# SparkFun_MicroMod_GNSS_Function_Board_ZE.net
KiCad netlist of a schematic drawn in EAGLE
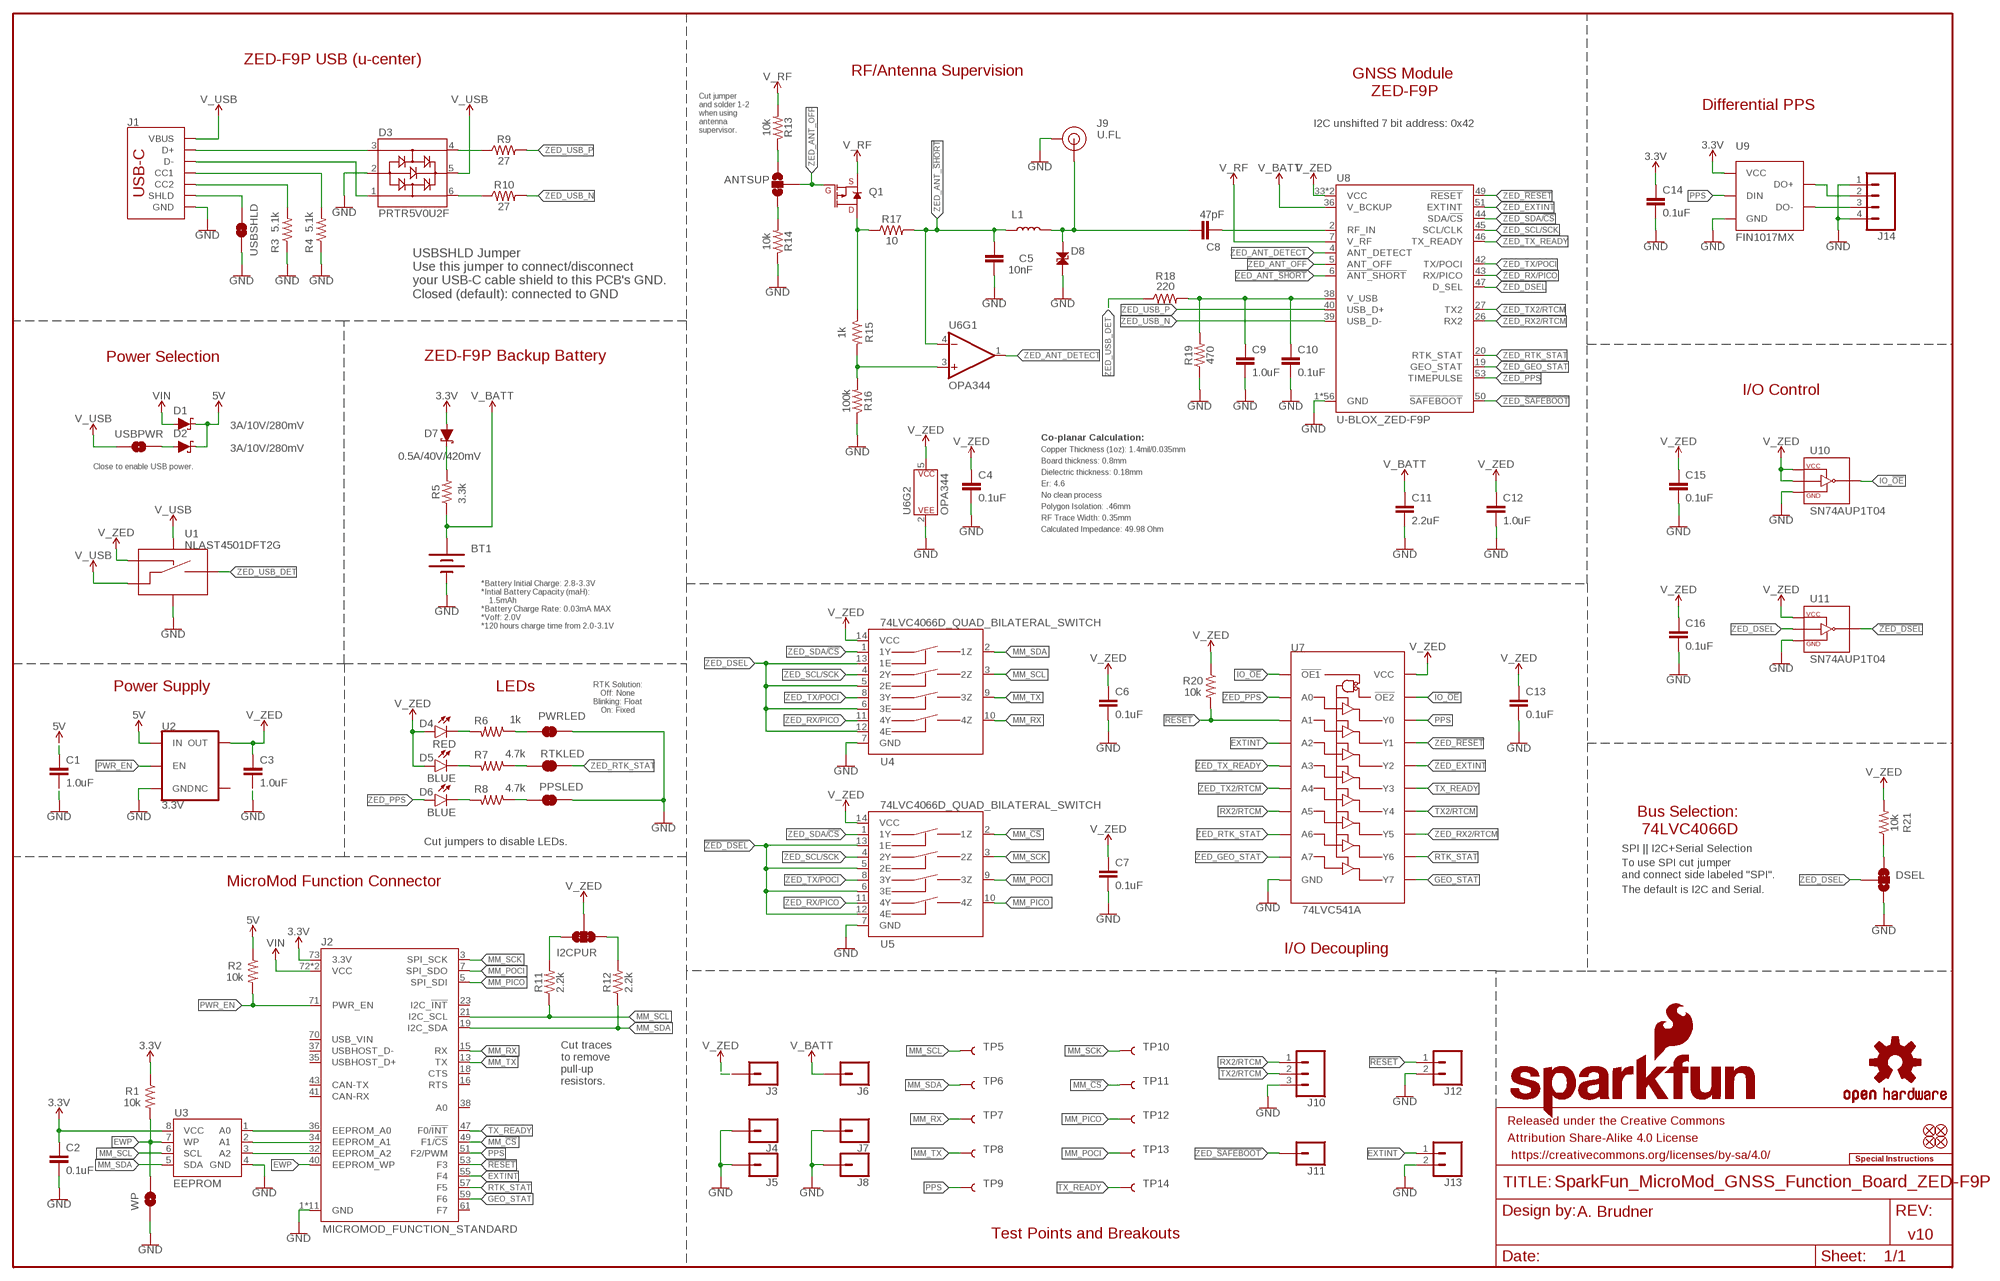
[diagram p0: schematic, sheet 1]

(export (version "E")
  (design (tool "Eeschema 10.0.6"))
  (components
    (comp (ref "ANTSUP")
      (value "JUMPER-SMT_3_1-NC_TRACE_SILK")
      (footprint "eagle-import:SMT-JUMPER_3_1-NC_TRACE_SILK")
      (libsource (lib "eagle-import") (part "JUMPER-SMT_3_1-NC_TRACE_SILK"))
    )
    (comp (ref "BT1")
      (value "RELOWABLE_BATTERY_MS421R")
      (footprint "eagle-import:MS421R_IV03E")
      (libsource (lib "eagle-import") (part "RELOWABLE_BATTERY_MS421R"))
    )
    (comp (ref "C1")
      (value "1.0uF")
      (footprint "eagle-import:0402-TIGHT")
      (libsource (lib "eagle-import") (part "1.0UF-0402T-16V-10%"))
    )
    (comp (ref "C2")
      (value "0.1uF")
      (footprint "eagle-import:0402-TIGHT")
      (libsource (lib "eagle-import") (part "0.1UF-0402T-16V-10%"))
    )
    (comp (ref "C3")
      (value "1.0uF")
      (footprint "eagle-import:0402-TIGHT")
      (libsource (lib "eagle-import") (part "1.0UF-0402T-16V-10%"))
    )
    (comp (ref "C4")
      (value "0.1uF")
      (footprint "eagle-import:0402-TIGHT")
      (libsource (lib "eagle-import") (part "0.1UF-0402T-16V-10%"))
    )
    (comp (ref "C5")
      (value "10nF")
      (footprint "eagle-import:0402-TIGHT")
      (libsource (lib "eagle-import") (part "10NF-0402T-25V-10%-X7R-WE"))
    )
    (comp (ref "C6")
      (value "0.1uF")
      (footprint "eagle-import:0402-TIGHT")
      (libsource (lib "eagle-import") (part "0.1UF-0402T-16V-10%"))
    )
    (comp (ref "C7")
      (value "0.1uF")
      (footprint "eagle-import:0402-TIGHT")
      (libsource (lib "eagle-import") (part "0.1UF-0402T-16V-10%"))
    )
    (comp (ref "C8")
      (value "47pF")
      (footprint "eagle-import:0402-TIGHT")
      (fields
        (field (name "TOLERANCE") "5%")
        (field (name "VOLTAGE") "50V")
        (field (name "CAPACITANCE") "47pF")
      )
      (libsource (lib "eagle-import") (part "CBR04C470J5GAC"))
    )
    (comp (ref "C9")
      (value "1.0uF")
      (footprint "eagle-import:0402-TIGHT")
      (libsource (lib "eagle-import") (part "1.0UF-0402T-16V-10%"))
    )
    (comp (ref "C10")
      (value "0.1uF")
      (footprint "eagle-import:0402-TIGHT")
      (libsource (lib "eagle-import") (part "0.1UF-0402T-16V-10%"))
    )
    (comp (ref "C11")
      (value "2.2uF")
      (footprint "eagle-import:0402-TIGHT")
      (libsource (lib "eagle-import") (part "2.2UF-0402_TIGHT-10V-10%-X5R"))
    )
    (comp (ref "C12")
      (value "1.0uF")
      (footprint "eagle-import:0402-TIGHT")
      (libsource (lib "eagle-import") (part "1.0UF-0402T-16V-10%"))
    )
    (comp (ref "C13")
      (value "0.1uF")
      (footprint "eagle-import:0402-TIGHT")
      (libsource (lib "eagle-import") (part "0.1UF-0402T-16V-10%"))
    )
    (comp (ref "C14")
      (value "0.1uF")
      (footprint "eagle-import:0402-TIGHT")
      (libsource (lib "eagle-import") (part "0.1UF-0402T-16V-10%"))
    )
    (comp (ref "C15")
      (value "0.1uF")
      (footprint "eagle-import:0402-TIGHT")
      (libsource (lib "eagle-import") (part "0.1UF-0402T-16V-10%"))
    )
    (comp (ref "C16")
      (value "0.1uF")
      (footprint "eagle-import:0402-TIGHT")
      (libsource (lib "eagle-import") (part "0.1UF-0402T-16V-10%"))
    )
    (comp (ref "D1")
      (value "3A/10V/280mV")
      (footprint "eagle-import:SOD-323")
      (libsource (lib "eagle-import") (part "DIODE-SCHOTTKY-BAT60A"))
    )
    (comp (ref "D2")
      (value "3A/10V/280mV")
      (footprint "eagle-import:SOD-323")
      (libsource (lib "eagle-import") (part "DIODE-SCHOTTKY-BAT60A"))
    )
    (comp (ref "D3")
      (value "PRTR5V0U2F")
      (footprint "eagle-import:SOT886")
      (libsource (lib "eagle-import") (part "PRTR5V0U2F"))
    )
    (comp (ref "D4")
      (value "RED")
      (footprint "eagle-import:LED-0603")
      (libsource (lib "eagle-import") (part "LED-RED0603"))
    )
    (comp (ref "D5")
      (value "BLUE")
      (footprint "eagle-import:LED-0603")
      (libsource (lib "eagle-import") (part "LED-BLUE0603"))
    )
    (comp (ref "D6")
      (value "BLUE")
      (footprint "eagle-import:LED-0603")
      (libsource (lib "eagle-import") (part "LED-BLUE0603"))
    )
    (comp (ref "D7")
      (value "0.5A/40V/420mV")
      (footprint "eagle-import:SOD-323")
      (libsource (lib "eagle-import") (part "DIODE-SCHOTTKY-PMEG4005EJ"))
    )
    (comp (ref "D8")
      (value "PESD0402-0402T")
      (footprint "eagle-import:0402-TIGHT")
      (libsource (lib "eagle-import") (part "PESD0402-0402T"))
    )
    (comp (ref "DSEL")
      (value "JUMPER-SMT_3_1-NC_TRACE_SILK")
      (footprint "eagle-import:SMT-JUMPER_3_1-NC_TRACE_SILK")
      (libsource (lib "eagle-import") (part "JUMPER-SMT_3_1-NC_TRACE_SILK"))
    )
    (comp (ref "FD1")
      (value "FIDUCIALUFIDUCIAL")
      (footprint "eagle-import:FIDUCIAL-MICRO")
      (libsource (lib "eagle-import") (part "FIDUCIALUFIDUCIAL"))
    )
    (comp (ref "FD2")
      (value "FIDUCIALUFIDUCIAL")
      (footprint "eagle-import:FIDUCIAL-MICRO")
      (libsource (lib "eagle-import") (part "FIDUCIALUFIDUCIAL"))
    )
    (comp (ref "FD3")
      (value "FIDUCIALUFIDUCIAL")
      (footprint "eagle-import:FIDUCIAL-MICRO")
      (libsource (lib "eagle-import") (part "FIDUCIALUFIDUCIAL"))
    )
    (comp (ref "FD4")
      (value "FIDUCIALUFIDUCIAL")
      (footprint "eagle-import:FIDUCIAL-MICRO")
      (libsource (lib "eagle-import") (part "FIDUCIALUFIDUCIAL"))
    )
    (comp (ref "FRAME1")
      (value "FRAME-LEDGER")
      (footprint "eagle-import:CREATIVE_COMMONS")
      (libsource (lib "eagle-import") (part "FRAME-LEDGER"))
    )
    (comp (ref "I2CPUR")
      (value "JUMPER-SMT_3_2-NC_TRACE_SILK")
      (footprint "eagle-import:SMT-JUMPER_3_2-NC_TRACE_SILK")
      (libsource (lib "eagle-import") (part "JUMPER-SMT_3_2-NC_TRACE_SILK"))
    )
    (comp (ref "J1")
      (value "USB Female Type C Connector")
      (footprint "eagle-import:USB-C-16P-4LAYER-ISOLATED")
      (libsource (lib "eagle-import") (part "USB_C_4-LAYER-ISOLATED"))
    )
    (comp (ref "J2")
      (value "MICROMOD_FUNCTION_STANDARD")
      (footprint "eagle-import:M.2-CARD-E-22_FUNCTION_STANDARD")
      (libsource (lib "eagle-import") (part "MICROMOD_FUNCTION_STANDARD"))
    )
    (comp (ref "J3")
      (value "CONN_01PTH_NO_SILK_YES_STOP")
      (footprint "eagle-import:1X01_NO_SILK")
      (libsource (lib "eagle-import") (part "CONN_01PTH_NO_SILK_YES_STOP"))
    )
    (comp (ref "J4")
      (value "CONN_01PTH_NO_SILK_YES_STOP")
      (footprint "eagle-import:1X01_NO_SILK")
      (libsource (lib "eagle-import") (part "CONN_01PTH_NO_SILK_YES_STOP"))
    )
    (comp (ref "J5")
      (value "CONN_01PTH_NO_SILK_YES_STOP")
      (footprint "eagle-import:1X01_NO_SILK")
      (libsource (lib "eagle-import") (part "CONN_01PTH_NO_SILK_YES_STOP"))
    )
    (comp (ref "J6")
      (value "CONN_01PTH_NO_SILK_SMALL")
      (footprint "eagle-import:1X01_SMALL")
      (libsource (lib "eagle-import") (part "CONN_01PTH_NO_SILK_SMALL"))
    )
    (comp (ref "J7")
      (value "CONN_01PTH_NO_SILK_YES_STOP")
      (footprint "eagle-import:1X01_NO_SILK")
      (libsource (lib "eagle-import") (part "CONN_01PTH_NO_SILK_YES_STOP"))
    )
    (comp (ref "J8")
      (value "CONN_01PTH_NO_SILK_YES_STOP")
      (footprint "eagle-import:1X01_NO_SILK")
      (libsource (lib "eagle-import") (part "CONN_01PTH_NO_SILK_YES_STOP"))
    )
    (comp (ref "J9")
      (value "U.FL")
      (footprint "eagle-import:U.FL")
      (libsource (lib "eagle-import") (part "U.FL2PIN"))
    )
    (comp (ref "J10")
      (value "455-1750-1-ND")
      (footprint "eagle-import:1X03_NO_SILK")
      (libsource (lib "eagle-import") (part "CONN_031X03_NO_SILK"))
    )
    (comp (ref "J11")
      (value "CONN_01PTH_NO_SILK_YES_STOP")
      (footprint "eagle-import:1X01_NO_SILK")
      (libsource (lib "eagle-import") (part "CONN_01PTH_NO_SILK_YES_STOP"))
    )
    (comp (ref "J12")
      (value "CONN_021X02_NO_SILK")
      (footprint "eagle-import:1X02_NO_SILK")
      (libsource (lib "eagle-import") (part "CONN_021X02_NO_SILK"))
    )
    (comp (ref "J13")
      (value "CONN_021X02_NO_SILK")
      (footprint "eagle-import:1X02_NO_SILK")
      (libsource (lib "eagle-import") (part "CONN_021X02_NO_SILK"))
    )
    (comp (ref "J14")
      (value "CONN_041X04_NO_SILK")
      (footprint "eagle-import:1X04_NO_SILK")
      (libsource (lib "eagle-import") (part "CONN_041X04_NO_SILK"))
    )
    (comp (ref "L1")
      (value "150nH")
      (footprint "eagle-import:0402_MURATA")
      (libsource (lib "eagle-import") (part "LQW15AWR15J80D"))
    )
    (comp (ref "LOGO1")
      (value "SFE_LOGO_NAME_FLAMEBLANK")
      (footprint "eagle-import:BLANK")
      (libsource (lib "eagle-import") (part "SFE_LOGO_NAME_FLAMEBLANK"))
    )
    (comp (ref "LOGO2")
      (value "SPECIAL_INSTRUCTIONS-ORDERING")
      (footprint "eagle-import:ORDERING_INSTRUCTIONS")
      (libsource (lib "eagle-import") (part "SPECIAL_INSTRUCTIONS-ORDERING"))
    )
    (comp (ref "LOGO3")
      (value "OSHW-LOGOMINI")
      (footprint "eagle-import:OSHW-LOGO-MINI")
      (libsource (lib "eagle-import") (part "OSHW-LOGOMINI"))
    )
    (comp (ref "PPSLED")
      (value "JUMPER-SMT_2_NC_TRACE_SILK")
      (footprint "eagle-import:SMT-JUMPER_2_NC_TRACE_SILK")
      (libsource (lib "eagle-import") (part "JUMPER-SMT_2_NC_TRACE_SILK"))
    )
    (comp (ref "PWRLED")
      (value "JUMPER-SMT_2_NC_TRACE_SILK")
      (footprint "eagle-import:SMT-JUMPER_2_NC_TRACE_SILK")
      (libsource (lib "eagle-import") (part "JUMPER-SMT_2_NC_TRACE_SILK"))
    )
    (comp (ref "Q1")
      (value "DMP21D0UT-7")
      (footprint "eagle-import:SOT523")
      (libsource (lib "eagle-import") (part "DMP21D0UT-7"))
    )
    (comp (ref "R1")
      (value "10k")
      (footprint "eagle-import:0402-TIGHT")
      (libsource (lib "eagle-import") (part "10KOHM-0402T-1/16W-1%"))
    )
    (comp (ref "R2")
      (value "10k")
      (footprint "eagle-import:0402-TIGHT")
      (libsource (lib "eagle-import") (part "10KOHM-0402T-1/16W-1%"))
    )
    (comp (ref "R3")
      (value "5.1k")
      (footprint "eagle-import:0402-TIGHT")
      (libsource (lib "eagle-import") (part "5.1KOHM-0402T-1/16W-1%"))
    )
    (comp (ref "R4")
      (value "5.1k")
      (footprint "eagle-import:0402-TIGHT")
      (libsource (lib "eagle-import") (part "5.1KOHM-0402T-1/16W-1%"))
    )
    (comp (ref "R5")
      (value "3.3K")
      (footprint "eagle-import:0402-TIGHT")
      (fields (field (name "RES") "3.3k"))
      (libsource (lib "eagle-import") (part "3.3KOHM-0402T-1/16W-1%"))
    )
    (comp (ref "R6")
      (value "1k")
      (footprint "eagle-import:0402-TIGHT")
      (libsource (lib "eagle-import") (part "1KOHM-0402T-1/16W-1%"))
    )
    (comp (ref "R7")
      (value "4.7k")
      (footprint "eagle-import:0402-TIGHT")
      (libsource (lib "eagle-import") (part "4.7KOHM-0402T-1/16W-1%"))
    )
    (comp (ref "R8")
      (value "4.7k")
      (footprint "eagle-import:0402-TIGHT")
      (libsource (lib "eagle-import") (part "4.7KOHM-0402T-1/16W-1%"))
    )
    (comp (ref "R9")
      (value "27")
      (footprint "eagle-import:0402-TIGHT")
      (libsource (lib "eagle-import") (part "27OHM"))
    )
    (comp (ref "R10")
      (value "27")
      (footprint "eagle-import:0402-TIGHT")
      (libsource (lib "eagle-import") (part "27OHM"))
    )
    (comp (ref "R11")
      (value "2.2k")
      (footprint "eagle-import:0402-TIGHT")
      (libsource (lib "eagle-import") (part "2.2KOHM-0402T-1/16W-1%"))
    )
    (comp (ref "R12")
      (value "2.2k")
      (footprint "eagle-import:0402-TIGHT")
      (libsource (lib "eagle-import") (part "2.2KOHM-0402T-1/16W-1%"))
    )
    (comp (ref "R13")
      (value "10k")
      (footprint "eagle-import:0402-TIGHT")
      (libsource (lib "eagle-import") (part "10KOHM-0402T-1/16W-1%"))
    )
    (comp (ref "R14")
      (value "10k")
      (footprint "eagle-import:0402-TIGHT")
      (libsource (lib "eagle-import") (part "10KOHM-0402T-1/16W-1%"))
    )
    (comp (ref "R15")
      (value "1k")
      (footprint "eagle-import:0402-TIGHT")
      (fields (field (name "RESISTANCE") "1k"))
      (libsource (lib "eagle-import") (part "1KOHM-0402T-1/16W-1%"))
    )
    (comp (ref "R16")
      (value "100k")
      (footprint "eagle-import:0402-TIGHT")
      (libsource (lib "eagle-import") (part "100KOHM-0402T-1/16W-1%"))
    )
    (comp (ref "R17")
      (value "10")
      (footprint "eagle-import:0603")
      (libsource (lib "eagle-import") (part "10OHM-0603-1/10W-1%"))
    )
    (comp (ref "R18")
      (value "220")
      (footprint "eagle-import:0402-TIGHT")
      (libsource (lib "eagle-import") (part "220OHM-0402-TIGHT-1/16W-1%"))
    )
    (comp (ref "R19")
      (value "470")
      (footprint "eagle-import:0402-TIGHT")
      (libsource (lib "eagle-import") (part "470OHM-0402-TIGHT-1/16W-1%"))
    )
    (comp (ref "R20")
      (value "10k")
      (footprint "eagle-import:0402-TIGHT")
      (libsource (lib "eagle-import") (part "10KOHM-0402T-1/16W-1%"))
    )
    (comp (ref "R21")
      (value "10k")
      (footprint "eagle-import:0402-TIGHT")
      (libsource (lib "eagle-import") (part "10KOHM-0402T-1/16W-1%"))
    )
    (comp (ref "RTKLED")
      (value "JUMPER-SMT_2_NC_TRACE_SILK")
      (footprint "eagle-import:SMT-JUMPER_2_NC_TRACE_SILK")
      (libsource (lib "eagle-import") (part "JUMPER-SMT_2_NC_TRACE_SILK"))
    )
    (comp (ref "TP5")
      (value "TEST-POINT3")
      (footprint "eagle-import:PAD.03X.03")
      (libsource (lib "eagle-import") (part "TEST-POINT3"))
    )
    (comp (ref "TP6")
      (value "TEST-POINT3")
      (footprint "eagle-import:PAD.03X.03")
      (libsource (lib "eagle-import") (part "TEST-POINT3"))
    )
    (comp (ref "TP7")
      (value "TEST-POINT3")
      (footprint "eagle-import:PAD.03X.03")
      (libsource (lib "eagle-import") (part "TEST-POINT3"))
    )
    (comp (ref "TP8")
      (value "TEST-POINT3")
      (footprint "eagle-import:PAD.03X.03")
      (libsource (lib "eagle-import") (part "TEST-POINT3"))
    )
    (comp (ref "TP9")
      (value "TEST-POINT3")
      (footprint "eagle-import:PAD.03X.03")
      (libsource (lib "eagle-import") (part "TEST-POINT3"))
    )
    (comp (ref "TP10")
      (value "TEST-POINT3")
      (footprint "eagle-import:PAD.03X.03")
      (libsource (lib "eagle-import") (part "TEST-POINT3"))
    )
    (comp (ref "TP11")
      (value "TEST-POINT3")
      (footprint "eagle-import:PAD.03X.03")
      (libsource (lib "eagle-import") (part "TEST-POINT3"))
    )
    (comp (ref "TP12")
      (value "TEST-POINT3")
      (footprint "eagle-import:PAD.03X.03")
      (libsource (lib "eagle-import") (part "TEST-POINT3"))
    )
    (comp (ref "TP13")
      (value "TEST-POINT3")
      (footprint "eagle-import:PAD.03X.03")
      (libsource (lib "eagle-import") (part "TEST-POINT3"))
    )
    (comp (ref "TP14")
      (value "TEST-POINT3")
      (footprint "eagle-import:PAD.03X.03")
      (libsource (lib "eagle-import") (part "TEST-POINT3"))
    )
    (comp (ref "U1")
      (value "NLAST4501DFT2G")
      (footprint "eagle-import:SOT353")
      (libsource (lib "eagle-import") (part "NLAST4501DFT2G"))
    )
    (comp (ref "U2")
      (value "3.3V")
      (footprint "eagle-import:SOT23-5")
      (libsource (lib "eagle-import") (part "V_REG_AP2112K-3.3V"))
    )
    (comp (ref "U3")
      (value "EEPROM")
      (footprint "eagle-import:SO08")
      (libsource (lib "eagle-import") (part "EEPROM-I2C512K"))
    )
    (comp (ref "U4")
      (value "74LVC4066D_QUAD_BILATERAL_SWITCH")
      (footprint "eagle-import:SO14")
      (libsource (lib "eagle-import") (part "74LVC4066D_QUAD_BILATERAL_SWITCH"))
    )
    (comp (ref "U5")
      (value "74LVC4066D_QUAD_BILATERAL_SWITCH")
      (footprint "eagle-import:SO14")
      (libsource (lib "eagle-import") (part "74LVC4066D_QUAD_BILATERAL_SWITCH"))
    )
    (comp (ref "U6")
      (value "OPA344")
      (footprint "eagle-import:SOT23-5")
      (libsource (lib "eagle-import") (part "OPA344"))
    )
    (comp (ref "U7")
      (value "74LVC541A")
      (footprint "eagle-import:DHVQFN20")
      (libsource (lib "eagle-import") (part "74LVC541ABQ"))
    )
    (comp (ref "U8")
      (value "U-BLOX_ZED-F9P")
      (footprint "eagle-import:ZED-F9P")
      (libsource (lib "eagle-import") (part "U-BLOX_ZED-F9P"))
    )
    (comp (ref "U9")
      (value "FIN1017MX")
      (footprint "eagle-import:SO08")
      (libsource (lib "eagle-import") (part "FIN1017MX"))
    )
    (comp (ref "U10")
      (value "SN74AUP1T04")
      (footprint "eagle-import:SC-70-5_DCK")
      (libsource (lib "eagle-import") (part "SN74AUP1T04DCK"))
    )
    (comp (ref "U11")
      (value "SN74AUP1T04")
      (footprint "eagle-import:SC-70-5_DCK")
      (libsource (lib "eagle-import") (part "SN74AUP1T04DCK"))
    )
    (comp (ref "USBPWR")
      (value "JUMPER-SMT_2_NO_SILK")
      (footprint "eagle-import:SMT-JUMPER_2_NO_SILK")
      (libsource (lib "eagle-import") (part "JUMPER-SMT_2_NO_SILK"))
    )
    (comp (ref "USBSHLD")
      (value "JUMPER-SMT_2_NC_TRACE_SILK")
      (footprint "eagle-import:SMT-JUMPER_2_NC_TRACE_SILK")
      (libsource (lib "eagle-import") (part "JUMPER-SMT_2_NC_TRACE_SILK"))
    )
    (comp (ref "WP")
      (value "JUMPER-SMT_2_NO_SILK")
      (footprint "eagle-import:SMT-JUMPER_2_NO_SILK")
      (libsource (lib "eagle-import") (part "JUMPER-SMT_2_NO_SILK"))
    )
  )
  (nets
    (net (code "1") (name "/IO_~{OE}") (class "Default")
      (node (ref "U10") (pin "4") (pinfunction "Y_4") (pintype "bidirectional"))
      (node (ref "U7") (pin "1") (pinfunction "~{OE1}_1") (pintype "input"))
      (node (ref "U7") (pin "19") (pinfunction "~{OE2}_19") (pintype "input"))
    )
    (net (code "2") (name "/MM_~{CS}") (class "Default")
      (node (ref "J2") (pin "49") (pinfunction "F1/~{CS}_49") (pintype "bidirectional"))
      (node (ref "TP11") (pin "1") (pinfunction "1_1") (pintype "bidirectional"))
      (node (ref "U5") (pin "2") (pinfunction "1Z_2") (pintype "bidirectional"))
    )
    (net (code "3") (name "/ZED_ANT_~{SHORT}") (class "Default")
      (node (ref "C5") (pin "1") (pinfunction "1_1") (pintype "passive"))
      (node (ref "L1") (pin "1") (pinfunction "1_1") (pintype "passive"))
      (node (ref "R17") (pin "2") (pinfunction "2_2") (pintype "passive"))
      (node (ref "U6") (pin "4") (pinfunction "-IN_4") (pintype "input"))
      (node (ref "U8") (pin "6") (pinfunction "~{ANT_SHORT}_6") (pintype "input"))
    )
    (net (code "4") (name "/ZED_SDA{slash}~{CS}") (class "Default")
      (node (ref "U4") (pin "1") (pinfunction "1Y_1") (pintype "bidirectional"))
      (node (ref "U5") (pin "1") (pinfunction "1Y_1") (pintype "bidirectional"))
      (node (ref "U8") (pin "44") (pinfunction "SDA/~{CS}_44") (pintype "bidirectional"))
    )
    (net (code "5") (name "/ZED_~{RESET}") (class "Default")
      (node (ref "U7") (pin "17") (pinfunction "Y1_17") (pintype "output"))
      (node (ref "U8") (pin "49") (pinfunction "~{RESET}_49") (pintype "input"))
    )
    (net (code "6") (name "/ZED_~{SAFEBOOT}") (class "Default")
      (node (ref "J11") (pin "1") (pinfunction "1_1") (pintype "passive"))
      (node (ref "U8") (pin "50") (pinfunction "~{SAFEBOOT}_50") (pintype "input"))
    )
    (net (code "7") (name "/~{RESET}") (class "Default")
      (node (ref "J12") (pin "1") (pinfunction "1_1") (pintype "passive"))
      (node (ref "J2") (pin "53") (pinfunction "F3_53") (pintype "bidirectional"))
      (node (ref "R20") (pin "2") (pinfunction "2_2") (pintype "passive"))
      (node (ref "U7") (pin "3") (pinfunction "A1_3") (pintype "input"))
    )
    (net (code "8") (name "/~{ZED_DSEL}") (class "Default")
      (node (ref "U11") (pin "4") (pinfunction "Y_4") (pintype "bidirectional"))
      (node (ref "U5") (pin "12") (pinfunction "4E_12") (pintype "bidirectional"))
      (node (ref "U5") (pin "13") (pinfunction "1E_13") (pintype "bidirectional"))
      (node (ref "U5") (pin "5") (pinfunction "2E_5") (pintype "bidirectional"))
      (node (ref "U5") (pin "6") (pinfunction "3E_6") (pintype "bidirectional"))
    )
    (net (code "9") (name "3.3V") (class "Default")
      (node (ref "C14") (pin "1") (pinfunction "1_1") (pintype "passive"))
      (node (ref "C2") (pin "1") (pinfunction "1_1") (pintype "passive"))
      (node (ref "D7") (pin "A") (pinfunction "A_A") (pintype "passive"))
      (node (ref "J2") (pin "73") (pinfunction "3.3V_73") (pintype "bidirectional"))
      (node (ref "R1") (pin "1") (pinfunction "1_1") (pintype "passive"))
      (node (ref "U3") (pin "8") (pinfunction "VCC_8") (pintype "power_in"))
      (node (ref "U9") (pin "1") (pinfunction "VCC_1") (pintype "bidirectional"))
    )
    (net (code "10") (name "5V") (class "Default")
      (node (ref "C1") (pin "1") (pinfunction "1_1") (pintype "passive"))
      (node (ref "D1") (pin "C") (pinfunction "C_C") (pintype "passive"))
      (node (ref "D2") (pin "C") (pinfunction "C_C") (pintype "passive"))
      (node (ref "R2") (pin "1") (pinfunction "1_1") (pintype "passive"))
      (node (ref "U2") (pin "1") (pinfunction "IN_1") (pintype "input"))
    )
    (net (code "11") (name "EWP") (class "Default")
      (node (ref "J2") (pin "40") (pinfunction "EEPROM_WP_40") (pintype "bidirectional"))
      (node (ref "R1") (pin "2") (pinfunction "2_2") (pintype "passive"))
      (node (ref "U3") (pin "7") (pinfunction "WP_7") (pintype "bidirectional"))
      (node (ref "WP") (pin "2") (pinfunction "2_2") (pintype "passive"))
    )
    (net (code "12") (name "EXTINT") (class "Default")
      (node (ref "J13") (pin "1") (pinfunction "1_1") (pintype "passive"))
      (node (ref "J2") (pin "55") (pinfunction "F4_55") (pintype "bidirectional"))
      (node (ref "U7") (pin "4") (pinfunction "A2_4") (pintype "input"))
    )
    (net (code "13") (name "GEO_STAT") (class "Default")
      (node (ref "J2") (pin "59") (pinfunction "F6_59") (pintype "bidirectional"))
      (node (ref "U7") (pin "11") (pinfunction "Y7_11") (pintype "output"))
    )
    (net (code "14") (name "GND") (class "Default")
      (node (ref "BT1") (pin "-") (pinfunction "-_-") (pintype "power_in"))
      (node (ref "C1") (pin "2") (pinfunction "2_2") (pintype "passive"))
      (node (ref "C10") (pin "2") (pinfunction "2_2") (pintype "passive"))
      (node (ref "C11") (pin "2") (pinfunction "2_2") (pintype "passive"))
      (node (ref "C12") (pin "2") (pinfunction "2_2") (pintype "passive"))
      (node (ref "C13") (pin "2") (pinfunction "2_2") (pintype "passive"))
      (node (ref "C14") (pin "2") (pinfunction "2_2") (pintype "passive"))
      (node (ref "C15") (pin "2") (pinfunction "2_2") (pintype "passive"))
      (node (ref "C16") (pin "2") (pinfunction "2_2") (pintype "passive"))
      (node (ref "C2") (pin "2") (pinfunction "2_2") (pintype "passive"))
      (node (ref "C3") (pin "2") (pinfunction "2_2") (pintype "passive"))
      (node (ref "C4") (pin "2") (pinfunction "2_2") (pintype "passive"))
      (node (ref "C5") (pin "2") (pinfunction "2_2") (pintype "passive"))
      (node (ref "C6") (pin "2") (pinfunction "2_2") (pintype "passive"))
      (node (ref "C7") (pin "2") (pinfunction "2_2") (pintype "passive"))
      (node (ref "C9") (pin "2") (pinfunction "2_2") (pintype "passive"))
      (node (ref "D3") (pin "2") (pinfunction "2_2") (pintype "power_in"))
      (node (ref "D8") (pin "2") (pinfunction "2_2") (pintype "bidirectional"))
      (node (ref "DSEL") (pin "1") (pinfunction "1_1") (pintype "passive"))
      (node (ref "J1") (pin "GND") (pinfunction "GND_GND") (pintype "bidirectional"))
      (node (ref "J1") (pin "GND2") (pinfunction "GND_GND2") (pintype "bidirectional"))
      (node (ref "J10") (pin "3") (pinfunction "3_3") (pintype "passive"))
      (node (ref "J12") (pin "2") (pinfunction "2_2") (pintype "passive"))
      (node (ref "J13") (pin "2") (pinfunction "2_2") (pintype "passive"))
      (node (ref "J14") (pin "1") (pinfunction "1_1") (pintype "passive"))
      (node (ref "J14") (pin "4") (pinfunction "4_4") (pintype "passive"))
      (node (ref "J2") (pin "1") (pinfunction "GND_1") (pintype "bidirectional"))
      (node (ref "J2") (pin "33") (pinfunction "GND_33") (pintype "bidirectional"))
      (node (ref "J2") (pin "39") (pinfunction "GND_39") (pintype "bidirectional"))
      (node (ref "J2") (pin "45") (pinfunction "GND_45") (pintype "bidirectional"))
      (node (ref "J2") (pin "75") (pinfunction "GND_75") (pintype "bidirectional"))
      (node (ref "J2") (pin "GND1") (pinfunction "GND_GND1") (pintype "bidirectional"))
      (node (ref "J2") (pin "GND2") (pinfunction "GND_GND2") (pintype "bidirectional"))
      (node (ref "J2") (pin "GND3") (pinfunction "GND_GND3") (pintype "bidirectional"))
      (node (ref "J2") (pin "GND4") (pinfunction "GND_GND4") (pintype "bidirectional"))
      (node (ref "J2") (pin "GND5") (pinfunction "GND_GND5") (pintype "bidirectional"))
      (node (ref "J2") (pin "GND6") (pinfunction "GND_GND6") (pintype "bidirectional"))
      (node (ref "J4") (pin "1") (pinfunction "1_1") (pintype "passive"))
      (node (ref "J5") (pin "1") (pinfunction "1_1") (pintype "passive"))
      (node (ref "J7") (pin "1") (pinfunction "1_1") (pintype "passive"))
      (node (ref "J8") (pin "1") (pinfunction "1_1") (pintype "passive"))
      (node (ref "J9") (pin "1") (pinfunction "GND_1") (pintype "bidirectional"))
      (node (ref "J9") (pin "2") (pinfunction "GND_2") (pintype "bidirectional"))
      (node (ref "PPSLED") (pin "1") (pinfunction "1_1") (pintype "passive"))
      (node (ref "PWRLED") (pin "2") (pinfunction "2_2") (pintype "passive"))
      (node (ref "R14") (pin "1") (pinfunction "1_1") (pintype "passive"))
      (node (ref "R16") (pin "1") (pinfunction "1_1") (pintype "passive"))
      (node (ref "R19") (pin "1") (pinfunction "1_1") (pintype "passive"))
      (node (ref "R3") (pin "1") (pinfunction "1_1") (pintype "passive"))
      (node (ref "R4") (pin "1") (pinfunction "1_1") (pintype "passive"))
      (node (ref "U1") (pin "3") (pinfunction "GND_3") (pintype "power_in"))
      (node (ref "U10") (pin "3") (pinfunction "GND_3") (pintype "power_in"))
      (node (ref "U11") (pin "3") (pinfunction "GND_3") (pintype "power_in"))
      (node (ref "U2") (pin "2") (pinfunction "GND_2") (pintype "input"))
      (node (ref "U3") (pin "4") (pinfunction "GND_4") (pintype "power_in"))
      (node (ref "U4") (pin "7") (pinfunction "GND_7") (pintype "bidirectional"))
      (node (ref "U5") (pin "7") (pinfunction "GND_7") (pintype "bidirectional"))
      (node (ref "U6") (pin "2") (pinfunction "P$V-_2") (pintype "bidirectional"))
      (node (ref "U7") (pin "10") (pinfunction "GND_10") (pintype "power_in"))
      (node (ref "U7") (pin "EPAD") (pinfunction "GND_EPAD") (pintype "power_in"))
      (node (ref "U8") (pin "1") (pinfunction "GND_1") (pintype "power_in"))
      (node (ref "U8") (pin "100") (pinfunction "GND_100") (pintype "power_in"))
      (node (ref "U8") (pin "101") (pinfunction "GND_101") (pintype "power_in"))
      (node (ref "U8") (pin "102") (pinfunction "GND_102") (pintype "power_in"))
      (node (ref "U8") (pin "12") (pinfunction "GND_12") (pintype "power_in"))
      (node (ref "U8") (pin "14") (pinfunction "GND_14") (pintype "power_in"))
      (node (ref "U8") (pin "3") (pinfunction "GND_3") (pintype "power_in"))
      (node (ref "U8") (pin "32") (pinfunction "GND_32") (pintype "power_in"))
      (node (ref "U8") (pin "37") (pinfunction "GND_37") (pintype "power_in"))
      (node (ref "U8") (pin "41") (pinfunction "GND_41") (pintype "power_in"))
      (node (ref "U8") (pin "48") (pinfunction "GND_48") (pintype "power_in"))
      (node (ref "U8") (pin "55") (pinfunction "GND_55") (pintype "power_in"))
      (node (ref "U8") (pin "56") (pinfunction "GND_56") (pintype "power_in"))
      (node (ref "U8") (pin "57") (pinfunction "GND_57") (pintype "power_in"))
      (node (ref "U8") (pin "58") (pinfunction "GND_58") (pintype "power_in"))
      (node (ref "U8") (pin "59") (pinfunction "GND_59") (pintype "power_in"))
      (node (ref "U8") (pin "60") (pinfunction "GND_60") (pintype "power_in"))
      (node (ref "U8") (pin "61") (pinfunction "GND_61") (pintype "power_in"))
      (node (ref "U8") (pin "62") (pinfunction "GND_62") (pintype "power_in"))
      (node (ref "U8") (pin "63") (pinfunction "GND_63") (pintype "power_in"))
      (node (ref "U8") (pin "64") (pinfunction "GND_64") (pintype "power_in"))
      (node (ref "U8") (pin "65") (pinfunction "GND_65") (pintype "power_in"))
      (node (ref "U8") (pin "66") (pinfunction "GND_66") (pintype "power_in"))
      (node (ref "U8") (pin "67") (pinfunction "GND_67") (pintype "power_in"))
      (node (ref "U8") (pin "68") (pinfunction "GND_68") (pintype "power_in"))
      (node (ref "U8") (pin "69") (pinfunction "GND_69") (pintype "power_in"))
      (node (ref "U8") (pin "70") (pinfunction "GND_70") (pintype "power_in"))
      (node (ref "U8") (pin "71") (pinfunction "GND_71") (pintype "power_in"))
      (node (ref "U8") (pin "72") (pinfunction "GND_72") (pintype "power_in"))
      (node (ref "U8") (pin "73") (pinfunction "GND_73") (pintype "power_in"))
      (node (ref "U8") (pin "74") (pinfunction "GND_74") (pintype "power_in"))
      (node (ref "U8") (pin "75") (pinfunction "GND_75") (pintype "power_in"))
      (node (ref "U8") (pin "76") (pinfunction "GND_76") (pintype "power_in"))
      (node (ref "U8") (pin "77") (pinfunction "GND_77") (pintype "power_in"))
      (node (ref "U8") (pin "78") (pinfunction "GND_78") (pintype "power_in"))
      (node (ref "U8") (pin "79") (pinfunction "GND_79") (pintype "power_in"))
      (node (ref "U8") (pin "80") (pinfunction "GND_80") (pintype "power_in"))
      (node (ref "U8") (pin "81") (pinfunction "GND_81") (pintype "power_in"))
      (node (ref "U8") (pin "82") (pinfunction "GND_82") (pintype "power_in"))
      (node (ref "U8") (pin "83") (pinfunction "GND_83") (pintype "power_in"))
      (node (ref "U8") (pin "84") (pinfunction "GND_84") (pintype "power_in"))
      (node (ref "U8") (pin "85") (pinfunction "GND_85") (pintype "power_in"))
      (node (ref "U8") (pin "86") (pinfunction "GND_86") (pintype "power_in"))
      (node (ref "U8") (pin "87") (pinfunction "GND_87") (pintype "power_in"))
      (node (ref "U8") (pin "88") (pinfunction "GND_88") (pintype "power_in"))
      (node (ref "U8") (pin "89") (pinfunction "GND_89") (pintype "power_in"))
      (node (ref "U8") (pin "90") (pinfunction "GND_90") (pintype "power_in"))
      (node (ref "U8") (pin "91") (pinfunction "GND_91") (pintype "power_in"))
      (node (ref "U8") (pin "92") (pinfunction "GND_92") (pintype "power_in"))
      (node (ref "U8") (pin "93") (pinfunction "GND_93") (pintype "power_in"))
      (node (ref "U8") (pin "94") (pinfunction "GND_94") (pintype "power_in"))
      (node (ref "U8") (pin "95") (pinfunction "GND_95") (pintype "power_in"))
      (node (ref "U8") (pin "96") (pinfunction "GND_96") (pintype "power_in"))
      (node (ref "U8") (pin "97") (pinfunction "GND_97") (pintype "power_in"))
      (node (ref "U8") (pin "98") (pinfunction "GND_98") (pintype "power_in"))
      (node (ref "U8") (pin "99") (pinfunction "GND_99") (pintype "power_in"))
      (node (ref "U9") (pin "4") (pinfunction "GND_4") (pintype "bidirectional"))
      (node (ref "USBSHLD") (pin "2") (pinfunction "2_2") (pintype "passive"))
      (node (ref "WP") (pin "1") (pinfunction "1_1") (pintype "passive"))
    )
    (net (code "15") (name "MM_PICO") (class "Default")
      (node (ref "J2") (pin "5") (pinfunction "SPI_SDI_5") (pintype "bidirectional"))
      (node (ref "TP12") (pin "1") (pinfunction "1_1") (pintype "bidirectional"))
      (node (ref "U5") (pin "10") (pinfunction "4Z_10") (pintype "bidirectional"))
    )
    (net (code "16") (name "MM_POCI") (class "Default")
      (node (ref "J2") (pin "7") (pinfunction "SPI_SDO_7") (pintype "bidirectional"))
      (node (ref "TP13") (pin "1") (pinfunction "1_1") (pintype "bidirectional"))
      (node (ref "U5") (pin "9") (pinfunction "3Z_9") (pintype "bidirectional"))
    )
    (net (code "17") (name "MM_RX") (class "Default")
      (node (ref "J2") (pin "15") (pinfunction "RX_15") (pintype "bidirectional"))
      (node (ref "TP7") (pin "1") (pinfunction "1_1") (pintype "bidirectional"))
      (node (ref "U4") (pin "10") (pinfunction "4Z_10") (pintype "bidirectional"))
    )
    (net (code "18") (name "MM_SCK") (class "Default")
      (node (ref "J2") (pin "3") (pinfunction "SPI_SCK_3") (pintype "bidirectional"))
      (node (ref "TP10") (pin "1") (pinfunction "1_1") (pintype "bidirectional"))
      (node (ref "U5") (pin "3") (pinfunction "2Z_3") (pintype "bidirectional"))
    )
    (net (code "19") (name "MM_SCL") (class "Default")
      (node (ref "J2") (pin "21") (pinfunction "I2C_SCL_21") (pintype "bidirectional"))
      (node (ref "R11") (pin "1") (pinfunction "1_1") (pintype "passive"))
      (node (ref "TP5") (pin "1") (pinfunction "1_1") (pintype "bidirectional"))
      (node (ref "U3") (pin "6") (pinfunction "SCL_6") (pintype "bidirectional"))
      (node (ref "U4") (pin "3") (pinfunction "2Z_3") (pintype "bidirectional"))
    )
    (net (code "20") (name "MM_SDA") (class "Default")
      (node (ref "J2") (pin "19") (pinfunction "I2C_SDA_19") (pintype "bidirectional"))
      (node (ref "R12") (pin "1") (pinfunction "1_1") (pintype "passive"))
      (node (ref "TP6") (pin "1") (pinfunction "1_1") (pintype "bidirectional"))
      (node (ref "U3") (pin "5") (pinfunction "SDA_5") (pintype "bidirectional"))
      (node (ref "U4") (pin "2") (pinfunction "1Z_2") (pintype "bidirectional"))
    )
    (net (code "21") (name "MM_TX") (class "Default")
      (node (ref "J2") (pin "13") (pinfunction "TX_13") (pintype "bidirectional"))
      (node (ref "TP8") (pin "1") (pinfunction "1_1") (pintype "bidirectional"))
      (node (ref "U4") (pin "9") (pinfunction "3Z_9") (pintype "bidirectional"))
    )
    (net (code "22") (name "Net-(ANTSUP-Pad1)") (class "Default")
      (node (ref "ANTSUP") (pin "1") (pinfunction "1_1") (pintype "passive"))
      (node (ref "R13") (pin "1") (pinfunction "1_1") (pintype "passive"))
    )
    (net (code "23") (name "Net-(ANTSUP-Pad3)") (class "Default")
      (node (ref "ANTSUP") (pin "3") (pinfunction "3_3") (pintype "passive"))
      (node (ref "R14") (pin "2") (pinfunction "2_2") (pintype "passive"))
    )
    (net (code "24") (name "Net-(D2-PadA)") (class "Default")
      (node (ref "D2") (pin "A") (pinfunction "A_A") (pintype "passive"))
      (node (ref "USBPWR") (pin "2") (pinfunction "2_2") (pintype "passive"))
    )
    (net (code "25") (name "Net-(D3-Pad1)") (class "Default")
      (node (ref "D3") (pin "1") (pinfunction "1_1") (pintype "bidirectional"))
      (node (ref "J1") (pin "A7") (pinfunction "D-_A7") (pintype "bidirectional"))
      (node (ref "J1") (pin "B7") (pinfunction "D-_B7") (pintype "bidirectional"))
    )
    (net (code "26") (name "Net-(D3-Pad3)") (class "Default")
      (node (ref "D3") (pin "3") (pinfunction "3_3") (pintype "bidirectional"))
      (node (ref "J1") (pin "A6") (pinfunction "D+_A6") (pintype "bidirectional"))
      (node (ref "J1") (pin "B6") (pinfunction "D+_B6") (pintype "bidirectional"))
    )
    (net (code "27") (name "Net-(D3-Pad4)") (class "Default")
      (node (ref "D3") (pin "4") (pinfunction "4_4") (pintype "bidirectional"))
      (node (ref "R9") (pin "1") (pinfunction "1_1") (pintype "passive"))
    )
    (net (code "28") (name "Net-(D3-Pad6)") (class "Default")
      (node (ref "D3") (pin "6") (pinfunction "6_6") (pintype "bidirectional"))
      (node (ref "R10") (pin "1") (pinfunction "1_1") (pintype "passive"))
    )
    (net (code "29") (name "Net-(D4-PadC)") (class "Default")
      (node (ref "D4") (pin "C") (pinfunction "C_C") (pintype "passive"))
      (node (ref "R6") (pin "2") (pinfunction "2_2") (pintype "passive"))
    )
    (net (code "30") (name "Net-(D5-PadC)") (class "Default")
      (node (ref "D5") (pin "C") (pinfunction "C_C") (pintype "passive"))
      (node (ref "R7") (pin "2") (pinfunction "2_2") (pintype "passive"))
    )
    (net (code "31") (name "Net-(D6-PadC)") (class "Default")
      (node (ref "D6") (pin "C") (pinfunction "C_C") (pintype "passive"))
      (node (ref "R8") (pin "2") (pinfunction "2_2") (pintype "passive"))
    )
    (net (code "32") (name "Net-(D7-PadC)") (class "Default")
      (node (ref "D7") (pin "C") (pinfunction "C_C") (pintype "passive"))
      (node (ref "R5") (pin "2") (pinfunction "2_2") (pintype "passive"))
    )
    (net (code "33") (name "Net-(DSEL-Pad3)") (class "Default")
      (node (ref "DSEL") (pin "3") (pinfunction "3_3") (pintype "passive"))
      (node (ref "R21") (pin "1") (pinfunction "1_1") (pintype "passive"))
    )
    (net (code "34") (name "Net-(I2CPUR-Pad1)") (class "Default")
      (node (ref "I2CPUR") (pin "1") (pinfunction "1_1") (pintype "passive"))
      (node (ref "R12") (pin "2") (pinfunction "2_2") (pintype "passive"))
    )
    (net (code "35") (name "Net-(I2CPUR-Pad3)") (class "Default")
      (node (ref "I2CPUR") (pin "3") (pinfunction "3_3") (pintype "passive"))
      (node (ref "R11") (pin "2") (pinfunction "2_2") (pintype "passive"))
    )
    (net (code "36") (name "Net-(J1-CC1)") (class "Default")
      (node (ref "J1") (pin "A5") (pinfunction "CC1_A5") (pintype "bidirectional"))
      (node (ref "R4") (pin "2") (pinfunction "2_2") (pintype "passive"))
    )
    (net (code "37") (name "Net-(J1-CC2)") (class "Default")
      (node (ref "J1") (pin "B5") (pinfunction "CC2_B5") (pintype "bidirectional"))
      (node (ref "R3") (pin "2") (pinfunction "2_2") (pintype "passive"))
    )
    (net (code "38") (name "Net-(J1-SHLD-PadSHLD1)") (class "Default")
      (node (ref "J1") (pin "SHLD1") (pinfunction "SHLD_SHLD1") (pintype "bidirectional"))
      (node (ref "J1") (pin "SHLD2") (pinfunction "SHLD_SHLD2") (pintype "bidirectional"))
      (node (ref "J1") (pin "SHLD3") (pinfunction "SHLD_SHLD3") (pintype "bidirectional"))
      (node (ref "J1") (pin "SHLD4") (pinfunction "SHLD_SHLD4") (pintype "bidirectional"))
      (node (ref "J1") (pin "SHLD5") (pinfunction "SHLD_SHLD5") (pintype "bidirectional"))
      (node (ref "J1") (pin "SHLD6") (pinfunction "SHLD_SHLD6") (pintype "bidirectional"))
      (node (ref "J1") (pin "SHLD7") (pinfunction "SHLD_SHLD7") (pintype "bidirectional"))
      (node (ref "J1") (pin "SHLD8") (pinfunction "SHLD_SHLD8") (pintype "bidirectional"))
      (node (ref "USBSHLD") (pin "1") (pinfunction "1_1") (pintype "passive"))
    )
    (net (code "39") (name "Net-(J2-EEPROM_A0)") (class "Default")
      (node (ref "J2") (pin "36") (pinfunction "EEPROM_A0_36") (pintype "bidirectional"))
      (node (ref "U3") (pin "1") (pinfunction "A0_1") (pintype "bidirectional"))
    )
    (net (code "40") (name "Net-(J2-EEPROM_A1)") (class "Default")
      (node (ref "J2") (pin "34") (pinfunction "EEPROM_A1_34") (pintype "bidirectional"))
      (node (ref "U3") (pin "2") (pinfunction "A1_2") (pintype "bidirectional"))
    )
    (net (code "41") (name "Net-(J2-EEPROM_A2)") (class "Default")
      (node (ref "J2") (pin "32") (pinfunction "EEPROM_A2_32") (pintype "bidirectional"))
      (node (ref "U3") (pin "3") (pinfunction "A2_3") (pintype "bidirectional"))
    )
    (net (code "42") (name "Net-(J9-SIGNAL)") (class "Default")
      (node (ref "C8") (pin "1") (pinfunction "1_1") (pintype "passive"))
      (node (ref "D8") (pin "1") (pinfunction "1_1") (pintype "bidirectional"))
      (node (ref "J9") (pin "FEED") (pinfunction "SIGNAL_FEED") (pintype "bidirectional"))
      (node (ref "L1") (pin "2") (pinfunction "2_2") (pintype "passive"))
    )
    (net (code "43") (name "Net-(PPSLED-Pad2)") (class "Default")
      (node (ref "PPSLED") (pin "2") (pinfunction "2_2") (pintype "passive"))
      (node (ref "R8") (pin "1") (pinfunction "1_1") (pintype "passive"))
    )
    (net (code "44") (name "Net-(PWRLED-Pad1)") (class "Default")
      (node (ref "PWRLED") (pin "1") (pinfunction "1_1") (pintype "passive"))
      (node (ref "R6") (pin "1") (pinfunction "1_1") (pintype "passive"))
    )
    (net (code "45") (name "Net-(Q1-D)") (class "Default")
      (node (ref "Q1") (pin "1") (pinfunction "D_1") (pintype "bidirectional"))
      (node (ref "R15") (pin "1") (pinfunction "1_1") (pintype "passive"))
      (node (ref "R17") (pin "1") (pinfunction "1_1") (pintype "passive"))
    )
    (net (code "46") (name "Net-(R7-Pad1)") (class "Default")
      (node (ref "R7") (pin "1") (pinfunction "1_1") (pintype "passive"))
      (node (ref "RTKLED") (pin "2") (pinfunction "2_2") (pintype "passive"))
    )
    (net (code "47") (name "Net-(U6A-+IN)") (class "Default")
      (node (ref "R15") (pin "2") (pinfunction "2_2") (pintype "passive"))
      (node (ref "R16") (pin "2") (pinfunction "2_2") (pintype "passive"))
      (node (ref "U6") (pin "3") (pinfunction "+IN_3") (pintype "input"))
    )
    (net (code "48") (name "Net-(U8-RF_IN)") (class "Default")
      (node (ref "C8") (pin "2") (pinfunction "2_2") (pintype "passive"))
      (node (ref "U8") (pin "2") (pinfunction "RF_IN_2") (pintype "input"))
    )
    (net (code "49") (name "Net-(U8-V_USB)") (class "Default")
      (node (ref "C10") (pin "1") (pinfunction "1_1") (pintype "passive"))
      (node (ref "C9") (pin "1") (pinfunction "1_1") (pintype "passive"))
      (node (ref "R18") (pin "2") (pinfunction "2_2") (pintype "passive"))
      (node (ref "R19") (pin "2") (pinfunction "2_2") (pintype "passive"))
      (node (ref "U8") (pin "38") (pinfunction "V_USB_38") (pintype "power_in"))
    )
    (net (code "50") (name "Net-(U9-DO+)") (class "Default")
      (node (ref "J14") (pin "2") (pinfunction "2_2") (pintype "passive"))
      (node (ref "U9") (pin "7") (pinfunction "DO+_7") (pintype "bidirectional"))
    )
    (net (code "51") (name "Net-(U9-DO-)") (class "Default")
      (node (ref "J14") (pin "3") (pinfunction "3_3") (pintype "passive"))
      (node (ref "U9") (pin "8") (pinfunction "DO-_8") (pintype "bidirectional"))
    )
    (net (code "52") (name "PPS") (class "Default")
      (node (ref "J2") (pin "51") (pinfunction "F2/PWM_51") (pintype "bidirectional"))
      (node (ref "TP9") (pin "1") (pinfunction "1_1") (pintype "bidirectional"))
      (node (ref "U7") (pin "18") (pinfunction "Y0_18") (pintype "output"))
      (node (ref "U9") (pin "2") (pinfunction "DIN_2") (pintype "bidirectional"))
    )
    (net (code "53") (name "PWR_EN") (class "Default")
      (node (ref "J2") (pin "71") (pinfunction "PWR_EN_71") (pintype "bidirectional"))
      (node (ref "R2") (pin "2") (pinfunction "2_2") (pintype "passive"))
      (node (ref "U2") (pin "3") (pinfunction "EN_3") (pintype "input"))
    )
    (net (code "54") (name "RTK_STAT") (class "Default")
      (node (ref "J2") (pin "57") (pinfunction "F5_57") (pintype "bidirectional"))
      (node (ref "U7") (pin "12") (pinfunction "Y6_12") (pintype "output"))
    )
    (net (code "55") (name "RX2{slash}RTCM") (class "Default")
      (node (ref "J10") (pin "1") (pinfunction "1_1") (pintype "passive"))
      (node (ref "U7") (pin "7") (pinfunction "A5_7") (pintype "input"))
    )
    (net (code "56") (name "TX2{slash}RTCM") (class "Default")
      (node (ref "J10") (pin "2") (pinfunction "2_2") (pintype "passive"))
      (node (ref "U7") (pin "14") (pinfunction "Y4_14") (pintype "output"))
    )
    (net (code "57") (name "TX_READY") (class "Default")
      (node (ref "J2") (pin "47") (pinfunction "F0/~{INT}_47") (pintype "bidirectional"))
      (node (ref "TP14") (pin "1") (pinfunction "1_1") (pintype "bidirectional"))
      (node (ref "U7") (pin "15") (pinfunction "Y3_15") (pintype "output"))
    )
    (net (code "58") (name "VIN") (class "Default")
      (node (ref "D1") (pin "A") (pinfunction "A_A") (pintype "passive"))
      (node (ref "J2") (pin "72") (pinfunction "VCC_72") (pintype "bidirectional"))
      (node (ref "J2") (pin "74") (pinfunction "VCC_74") (pintype "bidirectional"))
    )
    (net (code "59") (name "V_BATT") (class "Default")
      (node (ref "BT1") (pin "+") (pinfunction "+_+") (pintype "power_in"))
      (node (ref "C11") (pin "1") (pinfunction "1_1") (pintype "passive"))
      (node (ref "J6") (pin "P$1") (pinfunction "1_P$1") (pintype "passive"))
      (node (ref "R5") (pin "1") (pinfunction "1_1") (pintype "passive"))
      (node (ref "U8") (pin "36") (pinfunction "V_BCKUP_36") (pintype "power_in"))
    )
    (net (code "60") (name "V_RF") (class "Default")
      (node (ref "Q1") (pin "2") (pinfunction "S_2") (pintype "bidirectional"))
      (node (ref "R13") (pin "2") (pinfunction "2_2") (pintype "passive"))
      (node (ref "U8") (pin "7") (pinfunction "V_RF_7") (pintype "output"))
    )
    (net (code "61") (name "V_USB") (class "Default")
      (node (ref "D3") (pin "5") (pinfunction "5_5") (pintype "power_in"))
      (node (ref "J1") (pin "VBUS1") (pinfunction "VBUS_VBUS1") (pintype "bidirectional"))
      (node (ref "J1") (pin "VBUS2") (pinfunction "VBUS_VBUS2") (pintype "bidirectional"))
      (node (ref "U1") (pin "1") (pinfunction "COM_1") (pintype "bidirectional"))
      (node (ref "U1") (pin "5") (pinfunction "VCC_5") (pintype "power_in"))
      (node (ref "USBPWR") (pin "1") (pinfunction "1_1") (pintype "passive"))
    )
    (net (code "62") (name "V_ZED") (class "Default")
      (node (ref "C12") (pin "1") (pinfunction "1_1") (pintype "passive"))
      (node (ref "C13") (pin "1") (pinfunction "1_1") (pintype "passive"))
      (node (ref "C15") (pin "1") (pinfunction "1_1") (pintype "passive"))
      (node (ref "C16") (pin "1") (pinfunction "1_1") (pintype "passive"))
      (node (ref "C3") (pin "1") (pinfunction "1_1") (pintype "passive"))
      (node (ref "C4") (pin "1") (pinfunction "1_1") (pintype "passive"))
      (node (ref "C6") (pin "1") (pinfunction "1_1") (pintype "passive"))
      (node (ref "C7") (pin "1") (pinfunction "1_1") (pintype "passive"))
      (node (ref "D4") (pin "A") (pinfunction "A_A") (pintype "passive"))
      (node (ref "D5") (pin "A") (pinfunction "A_A") (pintype "passive"))
      (node (ref "I2CPUR") (pin "2") (pinfunction "2_2") (pintype "passive"))
      (node (ref "J3") (pin "1") (pinfunction "1_1") (pintype "passive"))
      (node (ref "R20") (pin "1") (pinfunction "1_1") (pintype "passive"))
      (node (ref "R21") (pin "2") (pinfunction "2_2") (pintype "passive"))
      (node (ref "U1") (pin "4") (pinfunction "EN_4") (pintype "input"))
      (node (ref "U10") (pin "2") (pinfunction "A_2") (pintype "bidirectional"))
      (node (ref "U10") (pin "5") (pinfunction "VCC_5") (pintype "power_in"))
      (node (ref "U11") (pin "5") (pinfunction "VCC_5") (pintype "power_in"))
      (node (ref "U2") (pin "5") (pinfunction "OUT_5") (pintype "passive"))
      (node (ref "U4") (pin "14") (pinfunction "VCC_14") (pintype "bidirectional"))
      (node (ref "U5") (pin "14") (pinfunction "VCC_14") (pintype "bidirectional"))
      (node (ref "U6") (pin "5") (pinfunction "P$V+_5") (pintype "bidirectional"))
      (node (ref "U7") (pin "20") (pinfunction "VCC_20") (pintype "power_in"))
      (node (ref "U8") (pin "33") (pinfunction "VCC_33") (pintype "power_in"))
      (node (ref "U8") (pin "34") (pinfunction "VCC_34") (pintype "power_in"))
    )
    (net (code "63") (name "ZED_ANT_DETECT") (class "Default")
      (node (ref "U6") (pin "1") (pinfunction "OUT_1") (pintype "output"))
      (node (ref "U8") (pin "4") (pinfunction "ANT_DETECT_4") (pintype "input"))
    )
    (net (code "64") (name "ZED_ANT_OFF") (class "Default")
      (node (ref "ANTSUP") (pin "2") (pinfunction "2_2") (pintype "passive"))
      (node (ref "Q1") (pin "3") (pinfunction "G_3") (pintype "bidirectional"))
      (node (ref "U8") (pin "5") (pinfunction "ANT_OFF_5") (pintype "output"))
    )
    (net (code "65") (name "ZED_DSEL") (class "Default")
      (node (ref "DSEL") (pin "2") (pinfunction "2_2") (pintype "passive"))
      (node (ref "U11") (pin "2") (pinfunction "A_2") (pintype "bidirectional"))
      (node (ref "U4") (pin "12") (pinfunction "4E_12") (pintype "bidirectional"))
      (node (ref "U4") (pin "13") (pinfunction "1E_13") (pintype "bidirectional"))
      (node (ref "U4") (pin "5") (pinfunction "2E_5") (pintype "bidirectional"))
      (node (ref "U4") (pin "6") (pinfunction "3E_6") (pintype "bidirectional"))
      (node (ref "U8") (pin "47") (pinfunction "D_SEL_47") (pintype "input"))
    )
    (net (code "66") (name "ZED_EXTINT") (class "Default")
      (node (ref "U7") (pin "16") (pinfunction "Y2_16") (pintype "output"))
      (node (ref "U8") (pin "51") (pinfunction "EXTINT_51") (pintype "input"))
    )
    (net (code "67") (name "ZED_GEO_STAT") (class "Default")
      (node (ref "U7") (pin "9") (pinfunction "A7_9") (pintype "input"))
      (node (ref "U8") (pin "19") (pinfunction "GEO_STAT_19") (pintype "output"))
    )
    (net (code "68") (name "ZED_PPS") (class "Default")
      (node (ref "D6") (pin "A") (pinfunction "A_A") (pintype "passive"))
      (node (ref "U7") (pin "2") (pinfunction "A0_2") (pintype "input"))
      (node (ref "U8") (pin "53") (pinfunction "TIMEPULSE_53") (pintype "output"))
    )
    (net (code "69") (name "ZED_RTK_STAT") (class "Default")
      (node (ref "RTKLED") (pin "1") (pinfunction "1_1") (pintype "passive"))
      (node (ref "U7") (pin "8") (pinfunction "A6_8") (pintype "input"))
      (node (ref "U8") (pin "20") (pinfunction "RTK_STAT_20") (pintype "output"))
    )
    (net (code "70") (name "ZED_RX2{slash}RTCM") (class "Default")
      (node (ref "U7") (pin "13") (pinfunction "Y5_13") (pintype "output"))
      (node (ref "U8") (pin "26") (pinfunction "RX2_26") (pintype "input"))
    )
    (net (code "71") (name "ZED_RX{slash}PICO") (class "Default")
      (node (ref "U4") (pin "11") (pinfunction "4Y_11") (pintype "bidirectional"))
      (node (ref "U5") (pin "11") (pinfunction "4Y_11") (pintype "bidirectional"))
      (node (ref "U8") (pin "43") (pinfunction "RX/PICO_43") (pintype "input"))
    )
    (net (code "72") (name "ZED_SCL{slash}SCK") (class "Default")
      (node (ref "U4") (pin "4") (pinfunction "2Y_4") (pintype "bidirectional"))
      (node (ref "U5") (pin "4") (pinfunction "2Y_4") (pintype "bidirectional"))
      (node (ref "U8") (pin "45") (pinfunction "SCL/CLK_45") (pintype "bidirectional"))
    )
    (net (code "73") (name "ZED_TX2{slash}RTCM") (class "Default")
      (node (ref "U7") (pin "6") (pinfunction "A4_6") (pintype "input"))
      (node (ref "U8") (pin "27") (pinfunction "TX2_27") (pintype "output"))
    )
    (net (code "74") (name "ZED_TX_READY") (class "Default")
      (node (ref "U7") (pin "5") (pinfunction "A3_5") (pintype "input"))
      (node (ref "U8") (pin "46") (pinfunction "TX_READY_46") (pintype "output"))
    )
    (net (code "75") (name "ZED_TX{slash}POCI") (class "Default")
      (node (ref "U4") (pin "8") (pinfunction "3Y_8") (pintype "bidirectional"))
      (node (ref "U5") (pin "8") (pinfunction "3Y_8") (pintype "bidirectional"))
      (node (ref "U8") (pin "42") (pinfunction "TX/POCI_42") (pintype "output"))
    )
    (net (code "76") (name "ZED_USB_DET") (class "Default")
      (node (ref "R18") (pin "1") (pinfunction "1_1") (pintype "passive"))
      (node (ref "U1") (pin "2") (pinfunction "NO_2") (pintype "bidirectional"))
    )
    (net (code "77") (name "ZED_USB_N") (class "Default")
      (node (ref "R10") (pin "2") (pinfunction "2_2") (pintype "passive"))
      (node (ref "U8") (pin "39") (pinfunction "USB_D-_39") (pintype "bidirectional"))
    )
    (net (code "78") (name "ZED_USB_P") (class "Default")
      (node (ref "R9") (pin "2") (pinfunction "2_2") (pintype "passive"))
      (node (ref "U8") (pin "40") (pinfunction "USB_D+_40") (pintype "bidirectional"))
    )
    (net (code "79") (name "unconnected-(J2-A0-Pad38)") (class "Default")
      (node (ref "J2") (pin "38") (pinfunction "A0_38") (pintype "bidirectional"))
    )
    (net (code "80") (name "unconnected-(J2-CAN-RX-Pad41)") (class "Default")
      (node (ref "J2") (pin "41") (pinfunction "CAN-RX_41") (pintype "bidirectional"))
    )
    (net (code "81") (name "unconnected-(J2-CAN-TX-Pad43)") (class "Default")
      (node (ref "J2") (pin "43") (pinfunction "CAN-TX_43") (pintype "bidirectional"))
    )
    (net (code "82") (name "unconnected-(J2-CTS-Pad18)") (class "Default")
      (node (ref "J2") (pin "18") (pinfunction "CTS_18") (pintype "bidirectional"))
    )
    (net (code "83") (name "unconnected-(J2-F7-Pad61)") (class "Default")
      (node (ref "J2") (pin "61") (pinfunction "F7_61") (pintype "bidirectional"))
    )
    (net (code "84") (name "unconnected-(J2-I2C_~{INT}-Pad23)") (class "Default")
      (node (ref "J2") (pin "23") (pinfunction "I2C_~{INT}_23") (pintype "bidirectional"))
    )
    (net (code "85") (name "unconnected-(J2-RTS-Pad16)") (class "Default")
      (node (ref "J2") (pin "16") (pinfunction "RTS_16") (pintype "bidirectional"))
    )
    (net (code "86") (name "unconnected-(J2-USBHOST_D+-Pad35)") (class "Default")
      (node (ref "J2") (pin "35") (pinfunction "USBHOST_D+_35") (pintype "bidirectional"))
    )
    (net (code "87") (name "unconnected-(J2-USBHOST_D--Pad37)") (class "Default")
      (node (ref "J2") (pin "37") (pinfunction "USBHOST_D-_37") (pintype "bidirectional"))
    )
    (net (code "88") (name "unconnected-(J2-USB_VIN-Pad70)") (class "Default")
      (node (ref "J2") (pin "70") (pinfunction "USB_VIN_70") (pintype "bidirectional"))
    )
    (net (code "89") (name "unconnected-(U2-NC-Pad4)") (class "Default")
      (node (ref "U2") (pin "4") (pinfunction "NC_4") (pintype "no_connect"))
    )
  )
)
